# Isolators_HV.net
KiCad netlist of a schematic drawn in Altium Designer
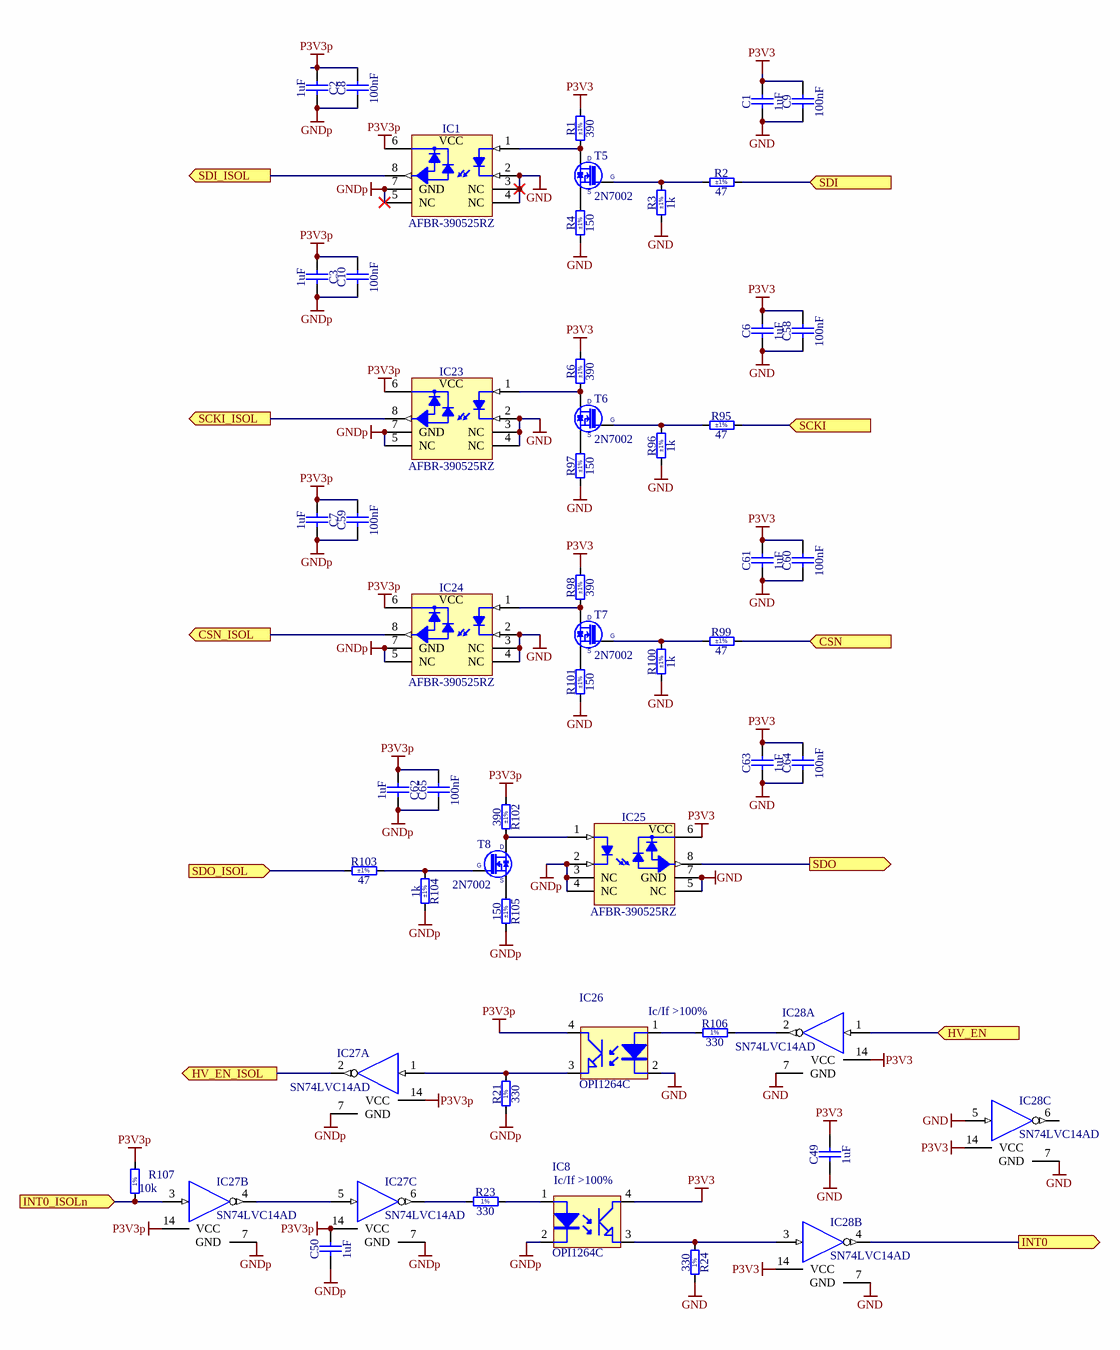
[diagram p0: Isolators_HV.SchDoc]

(export (version "E")
  (design (tool "Eeschema 10.0.6"))
  (components
    (comp (ref "C1")
      (value "1uF")
      (footprint "CAPC1005X55N")
      (description "Non-polarised capacitor")
      (fields
        (field (name "PART NUMBER") "CC0402_1UF_16V_10%_X5R")
        (field (name "VOLTAGE") "16V")
        (field (name "AUTHOR") "CERN DEM JLC")
      )
      (libsource (lib "Capacitors") (part "Capacitor - non polarized"))
    )
    (comp (ref "C2")
      (value "1uF")
      (footprint "CAPC1005X55N")
      (description "Non-polarised capacitor")
      (fields
        (field (name "PART NUMBER") "CC0402_1UF_16V_10%_X5R")
        (field (name "VOLTAGE") "16V")
        (field (name "AUTHOR") "CERN DEM JLC")
      )
      (libsource (lib "Capacitors") (part "Capacitor - non polarized"))
    )
    (comp (ref "C3")
      (value "1uF")
      (footprint "CAPC1005X55N")
      (description "Non-polarised capacitor")
      (fields
        (field (name "PART NUMBER") "CC0402_1UF_16V_10%_X5R")
        (field (name "VOLTAGE") "16V")
        (field (name "AUTHOR") "CERN DEM JLC")
      )
      (libsource (lib "Capacitors") (part "Capacitor - non polarized"))
    )
    (comp (ref "C6")
      (value "1uF")
      (footprint "CAPC1005X55N")
      (description "Non-polarised capacitor")
      (fields
        (field (name "PART NUMBER") "CC0402_1UF_16V_10%_X5R")
        (field (name "VOLTAGE") "16V")
        (field (name "AUTHOR") "CERN DEM JLC")
      )
      (libsource (lib "Capacitors") (part "Capacitor - non polarized"))
    )
    (comp (ref "C7")
      (value "1uF")
      (footprint "CAPC1005X55N")
      (description "Non-polarised capacitor")
      (fields
        (field (name "PART NUMBER") "CC0402_1UF_16V_10%_X5R")
        (field (name "VOLTAGE") "16V")
        (field (name "AUTHOR") "CERN DEM JLC")
      )
      (libsource (lib "Capacitors") (part "Capacitor - non polarized"))
    )
    (comp (ref "C8")
      (value "100nF")
      (footprint "CAPC1005X55N")
      (description "Non-polarised capacitor")
      (fields
        (field (name "PART NUMBER") "CC0402_100NF_16V_10%_X5R")
        (field (name "VOLTAGE") "16V")
        (field (name "AUTHOR") "CERN DEM JLC")
      )
      (libsource (lib "Capacitors") (part "Capacitor - non polarized"))
    )
    (comp (ref "C9")
      (value "100nF")
      (footprint "CAPC1005X55N")
      (description "Non-polarised capacitor")
      (fields
        (field (name "PART NUMBER") "CC0402_100NF_16V_10%_X5R")
        (field (name "VOLTAGE") "16V")
        (field (name "AUTHOR") "CERN DEM JLC")
      )
      (libsource (lib "Capacitors") (part "Capacitor - non polarized"))
    )
    (comp (ref "C10")
      (value "100nF")
      (footprint "CAPC1005X55N")
      (description "Non-polarised capacitor")
      (fields
        (field (name "PART NUMBER") "CC0402_100NF_16V_10%_X5R")
        (field (name "VOLTAGE") "16V")
        (field (name "AUTHOR") "CERN DEM JLC")
      )
      (libsource (lib "Capacitors") (part "Capacitor - non polarized"))
    )
    (comp (ref "C49")
      (value "1uF")
      (footprint "CAPC1005X55N")
      (description "Non-polarised capacitor")
      (fields
        (field (name "PART NUMBER") "CC0402_1UF_16V_10%_X5R")
        (field (name "VOLTAGE") "16V")
        (field (name "AUTHOR") "CERN DEM JLC")
      )
      (libsource (lib "Capacitors") (part "Capacitor - non polarized"))
    )
    (comp (ref "C50")
      (value "1uF")
      (footprint "CAPC1005X55N")
      (description "Non-polarised capacitor")
      (fields
        (field (name "PART NUMBER") "CC0402_1UF_16V_10%_X5R")
        (field (name "VOLTAGE") "16V")
        (field (name "AUTHOR") "CERN DEM JLC")
      )
      (libsource (lib "Capacitors") (part "Capacitor - non polarized"))
    )
    (comp (ref "C58")
      (value "100nF")
      (footprint "CAPC1005X55N")
      (description "Non-polarised capacitor")
      (fields
        (field (name "PART NUMBER") "CC0402_100NF_16V_10%_X5R")
        (field (name "VOLTAGE") "16V")
        (field (name "AUTHOR") "CERN DEM JLC")
      )
      (libsource (lib "Capacitors") (part "Capacitor - non polarized"))
    )
    (comp (ref "C59")
      (value "100nF")
      (footprint "CAPC1005X55N")
      (description "Non-polarised capacitor")
      (fields
        (field (name "PART NUMBER") "CC0402_100NF_16V_10%_X5R")
        (field (name "VOLTAGE") "16V")
        (field (name "AUTHOR") "CERN DEM JLC")
      )
      (libsource (lib "Capacitors") (part "Capacitor - non polarized"))
    )
    (comp (ref "C60")
      (value "100nF")
      (footprint "CAPC1005X55N")
      (description "Non-polarised capacitor")
      (fields
        (field (name "PART NUMBER") "CC0402_100NF_16V_10%_X5R")
        (field (name "VOLTAGE") "16V")
        (field (name "AUTHOR") "CERN DEM JLC")
      )
      (libsource (lib "Capacitors") (part "Capacitor - non polarized"))
    )
    (comp (ref "C61")
      (value "1uF")
      (footprint "CAPC1005X55N")
      (description "Non-polarised capacitor")
      (fields
        (field (name "PART NUMBER") "CC0402_1UF_16V_10%_X5R")
        (field (name "VOLTAGE") "16V")
        (field (name "AUTHOR") "CERN DEM JLC")
      )
      (libsource (lib "Capacitors") (part "Capacitor - non polarized"))
    )
    (comp (ref "C62")
      (value "1uF")
      (footprint "CAPC1005X55N")
      (description "Non-polarised capacitor")
      (fields
        (field (name "PART NUMBER") "CC0402_1UF_16V_10%_X5R")
        (field (name "VOLTAGE") "16V")
        (field (name "AUTHOR") "CERN DEM JLC")
      )
      (libsource (lib "Capacitors") (part "Capacitor - non polarized"))
    )
    (comp (ref "C63")
      (value "1uF")
      (footprint "CAPC1005X55N")
      (description "Non-polarised capacitor")
      (fields
        (field (name "PART NUMBER") "CC0402_1UF_16V_10%_X5R")
        (field (name "VOLTAGE") "16V")
        (field (name "AUTHOR") "CERN DEM JLC")
      )
      (libsource (lib "Capacitors") (part "Capacitor - non polarized"))
    )
    (comp (ref "C64")
      (value "100nF")
      (footprint "CAPC1005X55N")
      (description "Non-polarised capacitor")
      (fields
        (field (name "PART NUMBER") "CC0402_100NF_16V_10%_X5R")
        (field (name "VOLTAGE") "16V")
        (field (name "AUTHOR") "CERN DEM JLC")
      )
      (libsource (lib "Capacitors") (part "Capacitor - non polarized"))
    )
    (comp (ref "C65")
      (value "100nF")
      (footprint "CAPC1005X55N")
      (description "Non-polarised capacitor")
      (fields
        (field (name "PART NUMBER") "CC0402_100NF_16V_10%_X5R")
        (field (name "VOLTAGE") "16V")
        (field (name "AUTHOR") "CERN DEM JLC")
      )
      (libsource (lib "Capacitors") (part "Capacitor - non polarized"))
    )
    (comp (ref "IC1")
      (value "AFBR-390525RZ")
      (footprint "BROADCOM_AFBR-390525RZ")
      (description "High Voltage Galvanic Insulation Link for DC to 5MBaud")
      (fields (field (name "MANUFACTURER") "BROADCOM") (field (name "AUTHOR") "CERN DEM HF"))
      (libsource (lib "ICs And Semiconductors") (part "AFBR-3905XXRZ"))
    )
    (comp (ref "IC8")
      (value "OPI1264C")
      (footprint "OPI1264C")
      (description "10kV opto-coupler")
      (libsource (lib "") (part "OPTO-OPI1264C_1"))
    )
    (comp (ref "IC23")
      (value "AFBR-390525RZ")
      (footprint "BROADCOM_AFBR-390525RZ")
      (description "High Voltage Galvanic Insulation Link for DC to 5MBaud")
      (fields (field (name "MANUFACTURER") "BROADCOM") (field (name "AUTHOR") "CERN DEM HF"))
      (libsource (lib "ICs And Semiconductors") (part "AFBR-3905XXRZ"))
    )
    (comp (ref "IC24")
      (value "AFBR-390525RZ")
      (footprint "BROADCOM_AFBR-390525RZ")
      (description "High Voltage Galvanic Insulation Link for DC to 5MBaud")
      (fields (field (name "MANUFACTURER") "BROADCOM") (field (name "AUTHOR") "CERN DEM HF"))
      (libsource (lib "ICs And Semiconductors") (part "AFBR-3905XXRZ"))
    )
    (comp (ref "IC25")
      (value "AFBR-390525RZ")
      (footprint "BROADCOM_AFBR-390525RZ")
      (description "High Voltage Galvanic Insulation Link for DC to 5MBaud")
      (fields (field (name "MANUFACTURER") "BROADCOM") (field (name "AUTHOR") "CERN DEM HF"))
      (libsource (lib "") (part "AFBR-3905XXRZ_1"))
    )
    (comp (ref "IC26")
      (value "OPI1264C")
      (footprint "OPI1264C")
      (description "10kV opto-coupler")
      (libsource (lib "LIBRARY_SCH") (part "OPTO-OPI1264C"))
    )
    (comp (ref "IC27")
      (value "SN74LVC14AD")
      (footprint "SOIC127P600X175-14N")
      (description "Hex Schmitt-Trigger Inverter")
      (fields (field (name "MANUFACTURER") "TEXAS INSTRUMENTS") (field (name "AUTHOR") "CERN DEM JMW"))
      (libsource (lib "ICs And Semiconductors") (part "7414"))
    )
    (comp (ref "IC28")
      (value "SN74LVC14AD")
      (footprint "SOIC127P600X175-14N")
      (description "Hex Schmitt-Trigger Inverter")
      (fields (field (name "MANUFACTURER") "TEXAS INSTRUMENTS") (field (name "AUTHOR") "CERN DEM JMW"))
      (libsource (lib "ICs And Semiconductors") (part "7414"))
    )
    (comp (ref "R1")
      (value "390")
      (footprint "RESC1608X55N")
      (description "Resistor - 1%")
      (fields
        (field (name "TOLERANCE") "±1%")
        (field (name "PART NUMBER") "R0603_390R_1%_0.1W_100PPM")
        (field (name "POWER") "0.1W")
        (field (name "AUTHOR") "CERN DEM JLC")
      )
      (libsource (lib "Resistors") (part "Resistor - 1%"))
    )
    (comp (ref "R2")
      (value "47")
      (footprint "RESC1005X40N")
      (description "Resistor - 1%")
      (fields
        (field (name "TOLERANCE") "±1%")
        (field (name "PART NUMBER") "R0402_47R_1%_0.0625W_100PPM")
        (field (name "POWER") "0.0625W")
        (field (name "AUTHOR") "CERN DEM JLC")
      )
      (libsource (lib "Resistors") (part "Resistor - 1%"))
    )
    (comp (ref "R3")
      (value "1k")
      (footprint "RESC1005X40N")
      (description "Resistor - 1%")
      (fields
        (field (name "TOLERANCE") "±1%")
        (field (name "PART NUMBER") "R0402_1K_1%_0.0625W_100PPM")
        (field (name "POWER") "0.0625W")
        (field (name "AUTHOR") "CERN DEM JLC")
      )
      (libsource (lib "Resistors") (part "Resistor - 1%"))
    )
    (comp (ref "R4")
      (value "150")
      (footprint "RESC1608X55N")
      (description "Resistor - 1%")
      (fields
        (field (name "TOLERANCE") "±1%")
        (field (name "PART NUMBER") "R0603_150R_1%_0.1W_100PPM")
        (field (name "POWER") "0.1W")
        (field (name "AUTHOR") "CERN DEM JLC")
      )
      (libsource (lib "Resistors") (part "Resistor - 1%"))
    )
    (comp (ref "R6")
      (value "390")
      (footprint "RESC1608X55N")
      (description "Resistor - 1%")
      (fields
        (field (name "TOLERANCE") "±1%")
        (field (name "PART NUMBER") "R0603_390R_1%_0.1W_100PPM")
        (field (name "POWER") "0.1W")
        (field (name "AUTHOR") "CERN DEM JLC")
      )
      (libsource (lib "Resistors") (part "Resistor - 1%"))
    )
    (comp (ref "R21")
      (value "330")
      (footprint "RESC1005X40N")
      (description "Resistor - 1%")
      (fields
        (field (name "PART NUMBER") "R0402_330R_1%_0.0625W_100PPM")
        (field (name "POWER") "0.0625W")
        (field (name "AUTHOR") "CERN DEM JLC")
      )
      (libsource (lib "") (part "Resistor - 1%_1"))
    )
    (comp (ref "R23")
      (value "330")
      (footprint "RESC1005X40N")
      (description "Resistor - 1%")
      (fields
        (field (name "PART NUMBER") "R0402_330R_1%_0.0625W_100PPM")
        (field (name "POWER") "0.0625W")
        (field (name "AUTHOR") "CERN DEM JLC")
      )
      (libsource (lib "") (part "Resistor - 1%_1"))
    )
    (comp (ref "R24")
      (value "330")
      (footprint "RESC1005X40N")
      (description "Resistor - 1%")
      (fields
        (field (name "PART NUMBER") "R0402_330R_1%_0.0625W_100PPM")
        (field (name "POWER") "0.0625W")
        (field (name "AUTHOR") "CERN DEM JLC")
      )
      (libsource (lib "") (part "Resistor - 1%_1"))
    )
    (comp (ref "R95")
      (value "47")
      (footprint "RESC1005X40N")
      (description "Resistor - 1%")
      (fields
        (field (name "TOLERANCE") "±1%")
        (field (name "PART NUMBER") "R0402_47R_1%_0.0625W_100PPM")
        (field (name "POWER") "0.0625W")
        (field (name "AUTHOR") "CERN DEM JLC")
      )
      (libsource (lib "Resistors") (part "Resistor - 1%"))
    )
    (comp (ref "R96")
      (value "1k")
      (footprint "RESC1005X40N")
      (description "Resistor - 1%")
      (fields
        (field (name "TOLERANCE") "±1%")
        (field (name "PART NUMBER") "R0402_1K_1%_0.0625W_100PPM")
        (field (name "POWER") "0.0625W")
        (field (name "AUTHOR") "CERN DEM JLC")
      )
      (libsource (lib "Resistors") (part "Resistor - 1%"))
    )
    (comp (ref "R97")
      (value "150")
      (footprint "RESC1608X55N")
      (description "Resistor - 1%")
      (fields
        (field (name "TOLERANCE") "±1%")
        (field (name "PART NUMBER") "R0603_150R_1%_0.1W_100PPM")
        (field (name "POWER") "0.1W")
        (field (name "AUTHOR") "CERN DEM JLC")
      )
      (libsource (lib "Resistors") (part "Resistor - 1%"))
    )
    (comp (ref "R98")
      (value "390")
      (footprint "RESC1608X55N")
      (description "Resistor - 1%")
      (fields
        (field (name "TOLERANCE") "±1%")
        (field (name "PART NUMBER") "R0603_390R_1%_0.1W_100PPM")
        (field (name "POWER") "0.1W")
        (field (name "AUTHOR") "CERN DEM JLC")
      )
      (libsource (lib "Resistors") (part "Resistor - 1%"))
    )
    (comp (ref "R99")
      (value "47")
      (footprint "RESC1005X40N")
      (description "Resistor - 1%")
      (fields
        (field (name "TOLERANCE") "±1%")
        (field (name "PART NUMBER") "R0402_47R_1%_0.0625W_100PPM")
        (field (name "POWER") "0.0625W")
        (field (name "AUTHOR") "CERN DEM JLC")
      )
      (libsource (lib "Resistors") (part "Resistor - 1%"))
    )
    (comp (ref "R100")
      (value "1k")
      (footprint "RESC1005X40N")
      (description "Resistor - 1%")
      (fields
        (field (name "TOLERANCE") "±1%")
        (field (name "PART NUMBER") "R0402_1K_1%_0.0625W_100PPM")
        (field (name "POWER") "0.0625W")
        (field (name "AUTHOR") "CERN DEM JLC")
      )
      (libsource (lib "Resistors") (part "Resistor - 1%"))
    )
    (comp (ref "R101")
      (value "150")
      (footprint "RESC1608X55N")
      (description "Resistor - 1%")
      (fields
        (field (name "TOLERANCE") "±1%")
        (field (name "PART NUMBER") "R0603_150R_1%_0.1W_100PPM")
        (field (name "POWER") "0.1W")
        (field (name "AUTHOR") "CERN DEM JLC")
      )
      (libsource (lib "Resistors") (part "Resistor - 1%"))
    )
    (comp (ref "R102")
      (value "390")
      (footprint "RESC1608X55N")
      (description "Resistor - 1%")
      (fields
        (field (name "TOLERANCE") "±1%")
        (field (name "PART NUMBER") "R0603_390R_1%_0.1W_100PPM")
        (field (name "POWER") "0.1W")
        (field (name "AUTHOR") "CERN DEM JLC")
      )
      (libsource (lib "Resistors") (part "Resistor - 1%"))
    )
    (comp (ref "R103")
      (value "47")
      (footprint "RESC1005X40N")
      (description "Resistor - 1%")
      (fields
        (field (name "TOLERANCE") "±1%")
        (field (name "PART NUMBER") "R0402_47R_1%_0.0625W_100PPM")
        (field (name "POWER") "0.0625W")
        (field (name "AUTHOR") "CERN DEM JLC")
      )
      (libsource (lib "Resistors") (part "Resistor - 1%"))
    )
    (comp (ref "R104")
      (value "1k")
      (footprint "RESC1005X40N")
      (description "Resistor - 1%")
      (fields
        (field (name "TOLERANCE") "±1%")
        (field (name "PART NUMBER") "R0402_1K_1%_0.0625W_100PPM")
        (field (name "POWER") "0.0625W")
        (field (name "AUTHOR") "CERN DEM JLC")
      )
      (libsource (lib "Resistors") (part "Resistor - 1%"))
    )
    (comp (ref "R105")
      (value "150")
      (footprint "RESC1608X55N")
      (description "Resistor - 1%")
      (fields
        (field (name "TOLERANCE") "±1%")
        (field (name "PART NUMBER") "R0603_150R_1%_0.1W_100PPM")
        (field (name "POWER") "0.1W")
        (field (name "AUTHOR") "CERN DEM JLC")
      )
      (libsource (lib "Resistors") (part "Resistor - 1%"))
    )
    (comp (ref "R106")
      (value "330")
      (footprint "RESC1005X40N")
      (description "Resistor - 1%")
      (fields
        (field (name "PART NUMBER") "R0402_330R_1%_0.0625W_100PPM")
        (field (name "POWER") "0.0625W")
        (field (name "AUTHOR") "CERN DEM JLC")
      )
      (libsource (lib "") (part "Resistor - 1%_1"))
    )
    (comp (ref "R107")
      (value "10k")
      (footprint "RESC1005X40N")
      (description "Resistor - 1%")
      (fields
        (field (name "PART NUMBER") "R0402_10K_1%_0.0625W_100PPM")
        (field (name "POWER") "0.0625W")
        (field (name "AUTHOR") "CERN DEM JLC")
      )
      (libsource (lib "") (part "Resistor - 1%_1"))
    )
    (comp (ref "T5")
      (value "2N7002")
      (footprint "SOT95P240X130-3N")
      (description "N-CHANNEL MOSFET WITH DIODE")
      (fields (field (name "MANUFACTURER") "FAIRCHILD SEMICONDUCTOR") (field (name "AUTHOR") "CERN DEM JLC"))
      (libsource (lib "") (part "N-MOSFET-D 1G 2S 3D_1"))
    )
    (comp (ref "T6")
      (value "2N7002")
      (footprint "SOT95P240X130-3N")
      (description "N-CHANNEL MOSFET WITH DIODE")
      (fields (field (name "MANUFACTURER") "FAIRCHILD SEMICONDUCTOR") (field (name "AUTHOR") "CERN DEM JLC"))
      (libsource (lib "") (part "N-MOSFET-D 1G 2S 3D_1"))
    )
    (comp (ref "T7")
      (value "2N7002")
      (footprint "SOT95P240X130-3N")
      (description "N-CHANNEL MOSFET WITH DIODE")
      (fields (field (name "MANUFACTURER") "FAIRCHILD SEMICONDUCTOR") (field (name "AUTHOR") "CERN DEM JLC"))
      (libsource (lib "") (part "N-MOSFET-D 1G 2S 3D_1"))
    )
    (comp (ref "T8")
      (value "2N7002")
      (footprint "SOT95P240X130-3N")
      (description "N-CHANNEL MOSFET WITH DIODE")
      (fields (field (name "MANUFACTURER") "FAIRCHILD SEMICONDUCTOR") (field (name "AUTHOR") "CERN DEM JLC"))
      (libsource (lib "ICs And Semiconductors") (part "N-MOSFET-D 1G 2S 3D"))
    )
  )
  (nets
    (net (code "1") (name "/CSN") (class "Default")
      (node (ref "R99") (pin "2") (pinfunction "2_2") (pintype "passive"))
    )
    (net (code "2") (name "/CSN_ISOL") (class "Default")
      (node (ref "IC24") (pin "8") (pinfunction "DATA_OUT_8") (pintype "output"))
    )
    (net (code "3") (name "/HV_EN") (class "Default")
      (node (ref "IC28") (pin "1") (pinfunction "IN_1") (pintype "input"))
    )
    (net (code "4") (name "/HV_EN_ISOL") (class "Default")
      (node (ref "IC27") (pin "2") (pinfunction "OUT_2") (pintype "output"))
    )
    (net (code "5") (name "/INT0") (class "Default")
      (node (ref "IC28") (pin "4") (pinfunction "OUT_4") (pintype "output"))
    )
    (net (code "6") (name "/INT0_ISOLn") (class "Default")
      (node (ref "IC27") (pin "3") (pinfunction "IN_3") (pintype "input"))
      (node (ref "R107") (pin "1") (pinfunction "1_1") (pintype "passive"))
    )
    (net (code "7") (name "/SCKI") (class "Default")
      (node (ref "R95") (pin "2") (pinfunction "2_2") (pintype "passive"))
    )
    (net (code "8") (name "/SCKI_ISOL") (class "Default")
      (node (ref "IC23") (pin "8") (pinfunction "DATA_OUT_8") (pintype "output"))
    )
    (net (code "9") (name "/SDI") (class "Default")
      (node (ref "R2") (pin "2") (pinfunction "2_2") (pintype "passive"))
    )
    (net (code "10") (name "/SDI_ISOL") (class "Default")
      (node (ref "IC1") (pin "8") (pinfunction "DATA_OUT_8") (pintype "output"))
    )
    (net (code "11") (name "/SDO") (class "Default")
      (node (ref "IC25") (pin "8") (pinfunction "DATA_OUT_8") (pintype "output"))
    )
    (net (code "12") (name "/SDO_ISOL") (class "Default")
      (node (ref "R103") (pin "2") (pinfunction "2_2") (pintype "passive"))
    )
    (net (code "13") (name "GND") (class "Default")
      (node (ref "C1") (pin "1") (pinfunction "1_1") (pintype "passive"))
      (node (ref "C49") (pin "2") (pinfunction "2_2") (pintype "passive"))
      (node (ref "C58") (pin "1") (pinfunction "1_1") (pintype "passive"))
      (node (ref "C6") (pin "1") (pinfunction "1_1") (pintype "passive"))
      (node (ref "C60") (pin "1") (pinfunction "1_1") (pintype "passive"))
      (node (ref "C61") (pin "1") (pinfunction "1_1") (pintype "passive"))
      (node (ref "C63") (pin "2") (pinfunction "2_2") (pintype "passive"))
      (node (ref "C64") (pin "1") (pinfunction "1_1") (pintype "passive"))
      (node (ref "C9") (pin "1") (pinfunction "1_1") (pintype "passive"))
      (node (ref "IC1") (pin "2") (pinfunction "C_2") (pintype "input"))
      (node (ref "IC1") (pin "3") (pinfunction "NC_3") (pintype "open_collector"))
      (node (ref "IC1") (pin "4") (pinfunction "NC_4") (pintype "open_collector"))
      (node (ref "IC23") (pin "2") (pinfunction "C_2") (pintype "input"))
      (node (ref "IC23") (pin "3") (pinfunction "NC_3") (pintype "open_collector"))
      (node (ref "IC23") (pin "4") (pinfunction "NC_4") (pintype "open_collector"))
      (node (ref "IC24") (pin "2") (pinfunction "C_2") (pintype "input"))
      (node (ref "IC24") (pin "3") (pinfunction "NC_3") (pintype "open_collector"))
      (node (ref "IC24") (pin "4") (pinfunction "NC_4") (pintype "open_collector"))
      (node (ref "IC25") (pin "5") (pinfunction "NC_5") (pintype "open_collector"))
      (node (ref "IC25") (pin "7") (pinfunction "GND_7") (pintype "power_in"))
      (node (ref "IC26") (pin "2") (pinfunction "K_2") (pintype "passive"))
      (node (ref "IC28") (pin "5") (pinfunction "IN_5") (pintype "input"))
      (node (ref "IC28") (pin "7") (pinfunction "GND_7") (pintype "power_in"))
      (node (ref "R100") (pin "1") (pinfunction "1_1") (pintype "passive"))
      (node (ref "R101") (pin "1") (pinfunction "1_1") (pintype "passive"))
      (node (ref "R24") (pin "1") (pinfunction "1_1") (pintype "passive"))
      (node (ref "R3") (pin "1") (pinfunction "1_1") (pintype "passive"))
      (node (ref "R4") (pin "1") (pinfunction "1_1") (pintype "passive"))
      (node (ref "R96") (pin "1") (pinfunction "1_1") (pintype "passive"))
      (node (ref "R97") (pin "1") (pinfunction "1_1") (pintype "passive"))
    )
    (net (code "14") (name "GNDp") (class "Default")
      (node (ref "C10") (pin "1") (pinfunction "1_1") (pintype "passive"))
      (node (ref "C2") (pin "2") (pinfunction "2_2") (pintype "passive"))
      (node (ref "C3") (pin "2") (pinfunction "2_2") (pintype "passive"))
      (node (ref "C50") (pin "2") (pinfunction "2_2") (pintype "passive"))
      (node (ref "C59") (pin "1") (pinfunction "1_1") (pintype "passive"))
      (node (ref "C62") (pin "1") (pinfunction "1_1") (pintype "passive"))
      (node (ref "C65") (pin "1") (pinfunction "1_1") (pintype "passive"))
      (node (ref "C7") (pin "2") (pinfunction "2_2") (pintype "passive"))
      (node (ref "C8") (pin "1") (pinfunction "1_1") (pintype "passive"))
      (node (ref "IC1") (pin "5") (pinfunction "NC_5") (pintype "open_collector"))
      (node (ref "IC1") (pin "7") (pinfunction "GND_7") (pintype "power_in"))
      (node (ref "IC23") (pin "5") (pinfunction "NC_5") (pintype "open_collector"))
      (node (ref "IC23") (pin "7") (pinfunction "GND_7") (pintype "power_in"))
      (node (ref "IC24") (pin "5") (pinfunction "NC_5") (pintype "open_collector"))
      (node (ref "IC24") (pin "7") (pinfunction "GND_7") (pintype "power_in"))
      (node (ref "IC25") (pin "2") (pinfunction "C_2") (pintype "input"))
      (node (ref "IC25") (pin "3") (pinfunction "NC_3") (pintype "open_collector"))
      (node (ref "IC25") (pin "4") (pinfunction "NC_4") (pintype "open_collector"))
      (node (ref "IC27") (pin "7") (pinfunction "GND_7") (pintype "power_in"))
      (node (ref "IC8") (pin "2") (pinfunction "K_2") (pintype "passive"))
      (node (ref "R104") (pin "1") (pinfunction "1_1") (pintype "passive"))
      (node (ref "R105") (pin "1") (pinfunction "1_1") (pintype "passive"))
      (node (ref "R21") (pin "1") (pinfunction "1_1") (pintype "passive"))
    )
    (net (code "15") (name "Net-(IC1-A)") (class "Default")
      (node (ref "IC1") (pin "1") (pinfunction "A_1") (pintype "input"))
      (node (ref "R1") (pin "1") (pinfunction "1_1") (pintype "passive"))
      (node (ref "T5") (pin "3") (pinfunction "D_3") (pintype "passive"))
    )
    (net (code "16") (name "Net-(IC8-A)") (class "Default")
      (node (ref "IC8") (pin "1") (pinfunction "A_1") (pintype "passive"))
      (node (ref "R23") (pin "1") (pinfunction "1_1") (pintype "passive"))
    )
    (net (code "17") (name "Net-(IC23-A)") (class "Default")
      (node (ref "IC23") (pin "1") (pinfunction "A_1") (pintype "input"))
      (node (ref "R6") (pin "1") (pinfunction "1_1") (pintype "passive"))
      (node (ref "T6") (pin "3") (pinfunction "D_3") (pintype "passive"))
    )
    (net (code "18") (name "Net-(IC24-A)") (class "Default")
      (node (ref "IC24") (pin "1") (pinfunction "A_1") (pintype "input"))
      (node (ref "R98") (pin "1") (pinfunction "1_1") (pintype "passive"))
      (node (ref "T7") (pin "3") (pinfunction "D_3") (pintype "passive"))
    )
    (net (code "19") (name "Net-(IC25-A)") (class "Default")
      (node (ref "IC25") (pin "1") (pinfunction "A_1") (pintype "input"))
      (node (ref "R102") (pin "1") (pinfunction "1_1") (pintype "passive"))
      (node (ref "T8") (pin "3") (pinfunction "D_3") (pintype "passive"))
    )
    (net (code "20") (name "Net-(IC26-A)") (class "Default")
      (node (ref "IC26") (pin "1") (pinfunction "A_1") (pintype "passive"))
      (node (ref "R106") (pin "1") (pinfunction "1_1") (pintype "passive"))
    )
    (net (code "21") (name "Net-(IC26-E)") (class "Default")
      (node (ref "IC26") (pin "3") (pinfunction "E_3") (pintype "passive"))
      (node (ref "IC27") (pin "1") (pinfunction "IN_1") (pintype "input"))
      (node (ref "R21") (pin "2") (pinfunction "2_2") (pintype "passive"))
    )
    (net (code "22") (name "Net-(IC27B-OUT)") (class "Default")
      (node (ref "IC27") (pin "4") (pinfunction "OUT_4") (pintype "output"))
      (node (ref "IC27") (pin "5") (pinfunction "IN_5") (pintype "input"))
    )
    (net (code "23") (name "Net-(IC27C-OUT)") (class "Default")
      (node (ref "IC27") (pin "6") (pinfunction "OUT_6") (pintype "output"))
      (node (ref "R23") (pin "2") (pinfunction "2_2") (pintype "passive"))
    )
    (net (code "24") (name "Net-(IC28A-OUT)") (class "Default")
      (node (ref "IC28") (pin "2") (pinfunction "OUT_2") (pintype "output"))
      (node (ref "R106") (pin "2") (pinfunction "2_2") (pintype "passive"))
    )
    (net (code "25") (name "Net-(IC28B-IN)") (class "Default")
      (node (ref "IC28") (pin "3") (pinfunction "IN_3") (pintype "input"))
      (node (ref "IC8") (pin "3") (pinfunction "E_3") (pintype "passive"))
      (node (ref "R24") (pin "2") (pinfunction "2_2") (pintype "passive"))
    )
    (net (code "26") (name "Net-(T5-G)") (class "Default")
      (node (ref "R2") (pin "1") (pinfunction "1_1") (pintype "passive"))
      (node (ref "R3") (pin "2") (pinfunction "2_2") (pintype "passive"))
      (node (ref "T5") (pin "1") (pinfunction "G_1") (pintype "passive"))
    )
    (net (code "27") (name "Net-(T5-S)") (class "Default")
      (node (ref "R4") (pin "2") (pinfunction "2_2") (pintype "passive"))
      (node (ref "T5") (pin "2") (pinfunction "S_2") (pintype "passive"))
    )
    (net (code "28") (name "Net-(T6-G)") (class "Default")
      (node (ref "R95") (pin "1") (pinfunction "1_1") (pintype "passive"))
      (node (ref "R96") (pin "2") (pinfunction "2_2") (pintype "passive"))
      (node (ref "T6") (pin "1") (pinfunction "G_1") (pintype "passive"))
    )
    (net (code "29") (name "Net-(T6-S)") (class "Default")
      (node (ref "R97") (pin "2") (pinfunction "2_2") (pintype "passive"))
      (node (ref "T6") (pin "2") (pinfunction "S_2") (pintype "passive"))
    )
    (net (code "30") (name "Net-(T7-G)") (class "Default")
      (node (ref "R100") (pin "2") (pinfunction "2_2") (pintype "passive"))
      (node (ref "R99") (pin "1") (pinfunction "1_1") (pintype "passive"))
      (node (ref "T7") (pin "1") (pinfunction "G_1") (pintype "passive"))
    )
    (net (code "31") (name "Net-(T7-S)") (class "Default")
      (node (ref "R101") (pin "2") (pinfunction "2_2") (pintype "passive"))
      (node (ref "T7") (pin "2") (pinfunction "S_2") (pintype "passive"))
    )
    (net (code "32") (name "Net-(T8-G)") (class "Default")
      (node (ref "R103") (pin "1") (pinfunction "1_1") (pintype "passive"))
      (node (ref "R104") (pin "2") (pinfunction "2_2") (pintype "passive"))
      (node (ref "T8") (pin "1") (pinfunction "G_1") (pintype "passive"))
    )
    (net (code "33") (name "Net-(T8-S)") (class "Default")
      (node (ref "R105") (pin "2") (pinfunction "2_2") (pintype "passive"))
      (node (ref "T8") (pin "2") (pinfunction "S_2") (pintype "passive"))
    )
    (net (code "34") (name "P3V3") (class "Default")
      (node (ref "C1") (pin "2") (pinfunction "2_2") (pintype "passive"))
      (node (ref "C49") (pin "1") (pinfunction "1_1") (pintype "passive"))
      (node (ref "C58") (pin "2") (pinfunction "2_2") (pintype "passive"))
      (node (ref "C6") (pin "2") (pinfunction "2_2") (pintype "passive"))
      (node (ref "C60") (pin "2") (pinfunction "2_2") (pintype "passive"))
      (node (ref "C61") (pin "2") (pinfunction "2_2") (pintype "passive"))
      (node (ref "C63") (pin "1") (pinfunction "1_1") (pintype "passive"))
      (node (ref "C64") (pin "2") (pinfunction "2_2") (pintype "passive"))
      (node (ref "C9") (pin "2") (pinfunction "2_2") (pintype "passive"))
      (node (ref "IC25") (pin "6") (pinfunction "VCC_6") (pintype "power_in"))
      (node (ref "IC28") (pin "14") (pinfunction "VCC_14") (pintype "power_in"))
      (node (ref "IC8") (pin "4") (pinfunction "C_4") (pintype "passive"))
      (node (ref "R1") (pin "2") (pinfunction "2_2") (pintype "passive"))
      (node (ref "R6") (pin "2") (pinfunction "2_2") (pintype "passive"))
      (node (ref "R98") (pin "2") (pinfunction "2_2") (pintype "passive"))
    )
    (net (code "35") (name "P3V3p") (class "Default")
      (node (ref "C10") (pin "2") (pinfunction "2_2") (pintype "passive"))
      (node (ref "C2") (pin "1") (pinfunction "1_1") (pintype "passive"))
      (node (ref "C3") (pin "1") (pinfunction "1_1") (pintype "passive"))
      (node (ref "C50") (pin "1") (pinfunction "1_1") (pintype "passive"))
      (node (ref "C59") (pin "2") (pinfunction "2_2") (pintype "passive"))
      (node (ref "C62") (pin "2") (pinfunction "2_2") (pintype "passive"))
      (node (ref "C65") (pin "2") (pinfunction "2_2") (pintype "passive"))
      (node (ref "C7") (pin "1") (pinfunction "1_1") (pintype "passive"))
      (node (ref "C8") (pin "2") (pinfunction "2_2") (pintype "passive"))
      (node (ref "IC1") (pin "6") (pinfunction "VCC_6") (pintype "power_in"))
      (node (ref "IC23") (pin "6") (pinfunction "VCC_6") (pintype "power_in"))
      (node (ref "IC24") (pin "6") (pinfunction "VCC_6") (pintype "power_in"))
      (node (ref "IC26") (pin "4") (pinfunction "C_4") (pintype "passive"))
      (node (ref "IC27") (pin "14") (pinfunction "VCC_14") (pintype "power_in"))
      (node (ref "R102") (pin "2") (pinfunction "2_2") (pintype "passive"))
      (node (ref "R107") (pin "2") (pinfunction "2_2") (pintype "passive"))
    )
    (net (code "36") (name "unconnected-(IC28C-OUT-Pad6)") (class "Default")
      (node (ref "IC28") (pin "6") (pinfunction "OUT_6") (pintype "output"))
    )
  )
)
